# DoorOpenerPCBv2.net
KiCad netlist of a schematic drawn in EAGLE
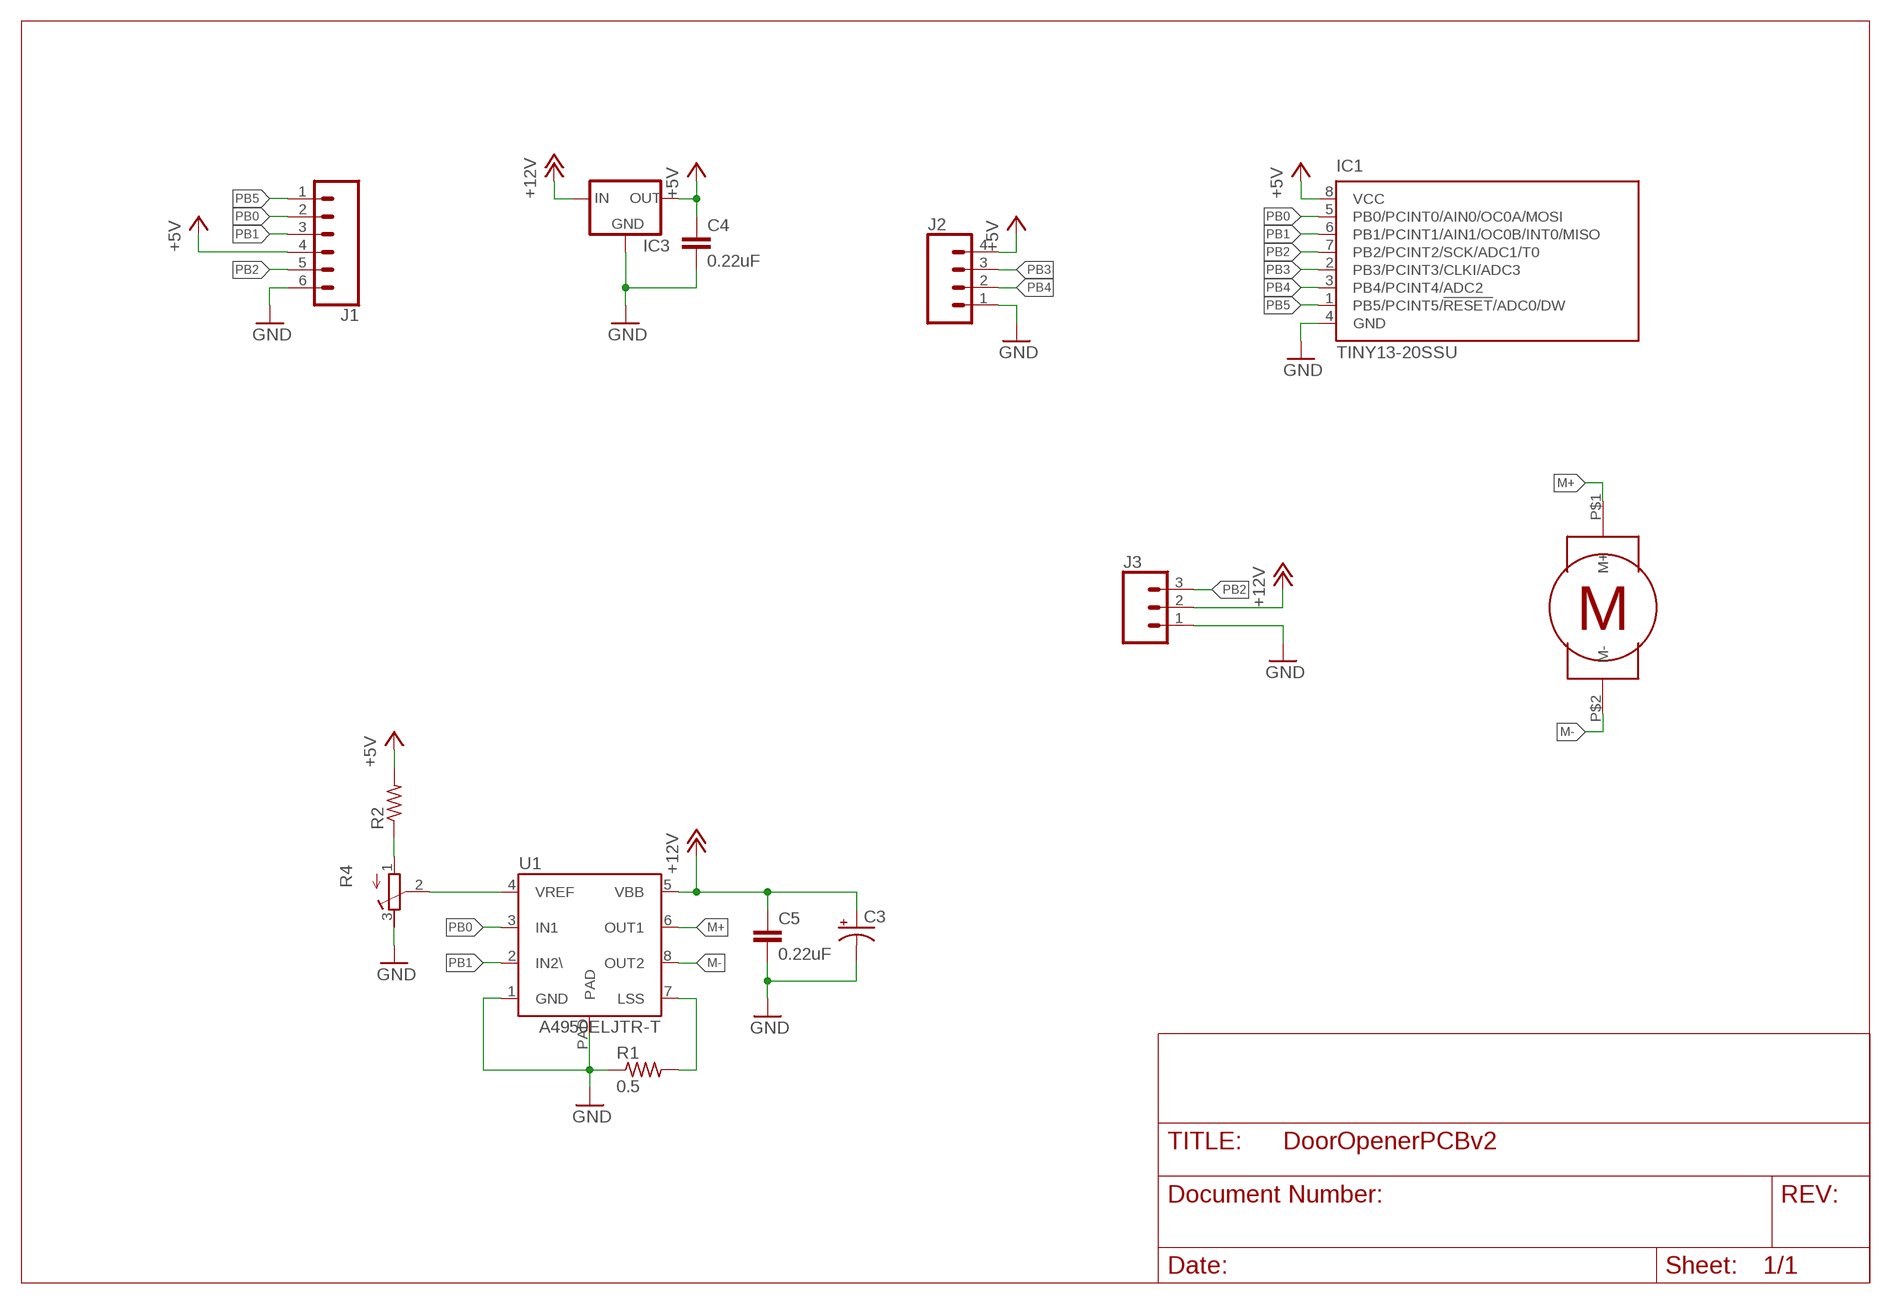
[diagram p0: schematic, sheet 1]

(export (version "E")
  (design (tool "Eeschema 10.0.6"))
  (components
    (comp (ref "C3")
      (value "CPOL-USCT3528")
      (footprint "eagle-import:CT3528")
      (libsource (lib "eagle-import") (part "CPOL-USCT3528"))
    )
    (comp (ref "C4")
      (value "0.22uF")
      (footprint "eagle-import:C0603K")
      (libsource (lib "eagle-import") (part "C-EUC0603K"))
    )
    (comp (ref "C5")
      (value "0.22uF")
      (footprint "eagle-import:C0603K")
      (libsource (lib "eagle-import") (part "C-EUC0603K"))
    )
    (comp (ref "IC1")
      (value "TINY13-20SSU")
      (footprint "eagle-import:8S1")
      (fields (field (name "MPN") "ATTINY13-20SSU"))
      (libsource (lib "eagle-import") (part "TINY13SSU-20"))
    )
    (comp (ref "IC3")
      (value "78LXX-SOT89R")
      (footprint "eagle-import:SOT89R")
      (libsource (lib "eagle-import") (part "78LXX-SOT89R"))
    )
    (comp (ref "J1")
      (value "CONN_061.27MM")
      (footprint "eagle-import:1X06_1.27MM")
      (libsource (lib "eagle-import") (part "CONN_061.27MM"))
    )
    (comp (ref "J2")
      (value "CONN_041.27MM")
      (footprint "eagle-import:1X04_1.27MM")
      (libsource (lib "eagle-import") (part "CONN_041.27MM"))
    )
    (comp (ref "J3")
      (value "CONN_03JST-PTH-NS")
      (footprint "eagle-import:JST-3-PTH-NS")
      (libsource (lib "eagle-import") (part "CONN_03JST-PTH-NS"))
    )
    (comp (ref "R1")
      (value "0.5")
      (footprint "eagle-import:R0805")
      (libsource (lib "eagle-import") (part "R-US_R0805"))
    )
    (comp (ref "R2")
      (value "R-US_R0603")
      (footprint "eagle-import:R0603")
      (libsource (lib "eagle-import") (part "R-US_R0603"))
    )
    (comp (ref "R4")
      (value "R-TRIMM3103")
      (footprint "eagle-import:RTRIM3103")
      (libsource (lib "eagle-import") (part "R-TRIMM3103"))
    )
    (comp (ref "U$2")
      (value "JGY-370")
      (footprint "eagle-import:PKG")
      (libsource (lib "eagle-import") (part "JGY-370"))
    )
    (comp (ref "U1")
      (value "A4950ELJTR-T")
      (footprint "eagle-import:SOIC8TP")
      (libsource (lib "eagle-import") (part "A4950ELJTR-T"))
    )
  )
  (nets
    (net (code "1") (name "+5V") (class "Default")
      (node (ref "C4") (pin "1") (pinfunction "1_1") (pintype "passive"))
      (node (ref "IC1") (pin "8") (pinfunction "VCC_8") (pintype "power_in"))
      (node (ref "IC3") (pin "2") (pinfunction "OUT_2") (pintype "passive"))
      (node (ref "J1") (pin "4") (pinfunction "4_4") (pintype "passive"))
      (node (ref "J2") (pin "4") (pinfunction "4_4") (pintype "passive"))
      (node (ref "R2") (pin "2") (pinfunction "2_2") (pintype "passive"))
    )
    (net (code "2") (name "+12V") (class "Default")
      (node (ref "C3") (pin "+") (pinfunction "+_+") (pintype "passive"))
      (node (ref "C5") (pin "1") (pinfunction "1_1") (pintype "passive"))
      (node (ref "IC3") (pin "1") (pinfunction "IN_1") (pintype "input"))
      (node (ref "J3") (pin "2") (pinfunction "2_2") (pintype "passive"))
      (node (ref "U1") (pin "5") (pinfunction "VBB_5") (pintype "bidirectional"))
    )
    (net (code "3") (name "GND") (class "Default")
      (node (ref "C3") (pin "-") (pinfunction "-_-") (pintype "passive"))
      (node (ref "C4") (pin "2") (pinfunction "2_2") (pintype "passive"))
      (node (ref "C5") (pin "2") (pinfunction "2_2") (pintype "passive"))
      (node (ref "IC1") (pin "4") (pinfunction "GND_4") (pintype "power_in"))
      (node (ref "IC3") (pin "3") (pinfunction "GND_3") (pintype "input"))
      (node (ref "IC3") (pin "4") (pinfunction "GND_4") (pintype "input"))
      (node (ref "J1") (pin "6") (pinfunction "6_6") (pintype "passive"))
      (node (ref "J2") (pin "1") (pinfunction "1_1") (pintype "passive"))
      (node (ref "J3") (pin "1") (pinfunction "1_1") (pintype "passive"))
      (node (ref "R1") (pin "1") (pinfunction "1_1") (pintype "passive"))
      (node (ref "R4") (pin "3") (pinfunction "E_3") (pintype "passive"))
      (node (ref "U1") (pin "1") (pinfunction "GND_1") (pintype "bidirectional"))
      (node (ref "U1") (pin "PAD") (pinfunction "PAD_PAD") (pintype "bidirectional"))
    )
    (net (code "4") (name "M+") (class "Default")
      (node (ref "U$2") (pin "P$1") (pinfunction "M+_P$1") (pintype "bidirectional"))
      (node (ref "U1") (pin "6") (pinfunction "OUT1_6") (pintype "bidirectional"))
    )
    (net (code "5") (name "M-") (class "Default")
      (node (ref "U$2") (pin "P$2") (pinfunction "M-_P$2") (pintype "bidirectional"))
      (node (ref "U1") (pin "8") (pinfunction "OUT2_8") (pintype "bidirectional"))
    )
    (net (code "6") (name "Net-(R4-A)") (class "Default")
      (node (ref "R2") (pin "1") (pinfunction "1_1") (pintype "passive"))
      (node (ref "R4") (pin "1") (pinfunction "A_1") (pintype "passive"))
    )
    (net (code "7") (name "Net-(R4-S)") (class "Default")
      (node (ref "R4") (pin "2") (pinfunction "S_2") (pintype "passive"))
      (node (ref "U1") (pin "4") (pinfunction "VREF_4") (pintype "bidirectional"))
    )
    (net (code "8") (name "Net-(U1-LSS)") (class "Default")
      (node (ref "R1") (pin "2") (pinfunction "2_2") (pintype "passive"))
      (node (ref "U1") (pin "7") (pinfunction "LSS_7") (pintype "bidirectional"))
    )
    (net (code "9") (name "PB0") (class "Default")
      (node (ref "IC1") (pin "5") (pinfunction "PB0/PCINT0/AIN0/OC0A/MOSI_5") (pintype "bidirectional"))
      (node (ref "J1") (pin "2") (pinfunction "2_2") (pintype "passive"))
      (node (ref "U1") (pin "3") (pinfunction "IN1_3") (pintype "bidirectional"))
    )
    (net (code "10") (name "PB1") (class "Default")
      (node (ref "IC1") (pin "6") (pinfunction "PB1/PCINT1/AIN1/OC0B/INT0/MISO_6") (pintype "bidirectional"))
      (node (ref "J1") (pin "3") (pinfunction "3_3") (pintype "passive"))
      (node (ref "U1") (pin "2") (pinfunction "IN2\\_2") (pintype "bidirectional"))
    )
    (net (code "11") (name "PB2") (class "Default")
      (node (ref "IC1") (pin "7") (pinfunction "PB2/PCINT2/SCK/ADC1/T0_7") (pintype "bidirectional"))
      (node (ref "J1") (pin "5") (pinfunction "5_5") (pintype "passive"))
      (node (ref "J3") (pin "3") (pinfunction "3_3") (pintype "passive"))
    )
    (net (code "12") (name "PB3") (class "Default")
      (node (ref "IC1") (pin "2") (pinfunction "PB3/PCINT3/CLKI/ADC3_2") (pintype "bidirectional"))
      (node (ref "J2") (pin "3") (pinfunction "3_3") (pintype "passive"))
    )
    (net (code "13") (name "PB4") (class "Default")
      (node (ref "IC1") (pin "3") (pinfunction "PB4/PCINT4/ADC2_3") (pintype "bidirectional"))
      (node (ref "J2") (pin "2") (pinfunction "2_2") (pintype "passive"))
    )
    (net (code "14") (name "PB5") (class "Default")
      (node (ref "IC1") (pin "1") (pinfunction "PB5/PCINT5/~{RESET}/ADC0/DW_1") (pintype "bidirectional"))
      (node (ref "J1") (pin "1") (pinfunction "1_1") (pintype "passive"))
    )
  )
)
